# 3V3_Buck.net
KiCad netlist of a schematic drawn in Altium Designer
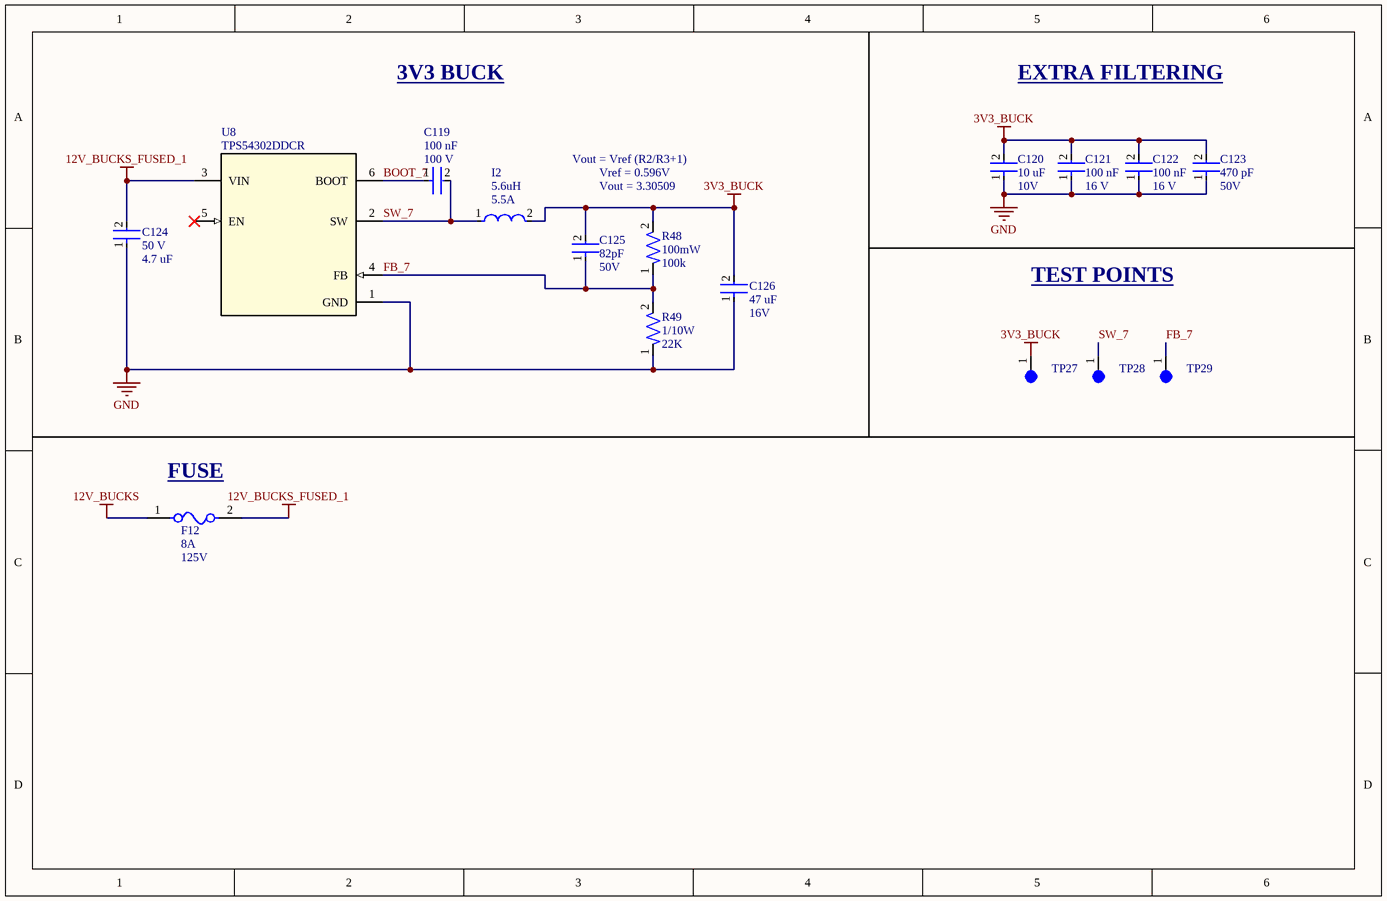
[diagram p0: 3V3_Buck.SchDoc]

(export (version "E")
  (design (tool "Eeschema 10.0.6"))
  (components
    (comp (ref "C119")
      (value "CC0603KRX7R0BB104")
      (footprint "CAP-0603")
      (description "CAP CER 0.1UF 100V X7R 0603")
      (fields (field (name "CAPACITANCE") "100 nF") (field (name "VOLTAGE") "100 V"))
      (libsource (lib "JLC_25") (part "CAP-100N-0001"))
    )
    (comp (ref "C120")
      (value "CC0603KRX5R6BB106")
      (footprint "CAP-0603")
      (description "CAP CER 10UF 10V X5R 0603")
      (fields (field (name "VOLTAGE") "10V") (field (name "CAPACITANCE") "10 uF"))
      (libsource (lib "JLC_25") (part "CAP-10U-0001"))
    )
    (comp (ref "C121")
      (value "CC0402KRX7R7BB104")
      (footprint "CAP-0402")
      (description "CAP CER 0.1UF 16V X7R 0402")
      (fields (field (name "VOLTAGE RATING") "16 V") (field (name "CAPACITANCE") "100 nF"))
      (libsource (lib "JLC_25") (part "CAP-0.1U-0001"))
    )
    (comp (ref "C122")
      (value "CC0402KRX7R7BB104")
      (footprint "CAP-0402")
      (description "CAP CER 0.1UF 16V X7R 0402")
      (fields (field (name "VOLTAGE RATING") "16 V") (field (name "CAPACITANCE") "100 nF"))
      (libsource (lib "JLC_25") (part "CAP-0.1U-0001"))
    )
    (comp (ref "C123")
      (value "CC0805JRNPO9BN471")
      (footprint "CAP-0805")
      (description "CAP CER 470PF 50V C0G/NPO 0805")
      (fields (field (name "VOLTAGE") "50V") (field (name "CAPACITANCE") "470 pF"))
      (libsource (lib "JLC_25") (part "CAP-470P-0001"))
    )
    (comp (ref "C124")
      (value "CC0805KKX5R9BB475")
      (footprint "CAP-0805")
      (description "CAP CER 4.7UF 50V X5R 0805")
      (fields (field (name "VOLTAGE") "50 V") (field (name "CAPACITANCE") "4.7 uF"))
      (libsource (lib "JLC_25") (part "CAP-4.7U-0002"))
    )
    (comp (ref "C125")
      (value "CC0805JRNPO9BN820")
      (footprint "CAP-0805")
      (description "82 pF ±5% 50V Ceramic Capacitor C0G, NP0 0805 (2012 Metric)")
      (fields (field (name "VOLTAGE") "50V") (field (name "CAPACITANCE") "82pF"))
      (libsource (lib "JLC_25") (part "CAP-82P-0001"))
    )
    (comp (ref "C126")
      (value "GRM32ER61C476KE15L")
      (footprint "CAP-1210")
      (description "CAP CER 47UF 16V X5R 1210")
      (fields (field (name "CAPACITANCE") "47 uF") (field (name "VOLTAGE") "16V"))
      (libsource (lib "JLC_25") (part "CAP-47U-0002"))
    )
    (comp (ref "F12")
      (value "01550900M")
      (footprint "FUSE-0001")
      (description "FUSE BLOK CARTRIDGE 125V 10A SMD")
      (fields (field (name "FUSE CURRENT") "8A") (field (name "VOLTAGE RATING") "125V"))
      (libsource (lib "JLC_25") (part "FUSE-0001"))
    )
    (comp (ref "I2")
      (value "SRP6540-5R6M")
      (footprint "IND_SRP6540-5R6M")
      (description "FIXED IND 5.6UH 5.5A 38 MOHM SMD")
      (fields (field (name "SATURATION CURRENT") "5.5A") (field (name "INDUCTANCE") "5.6uH"))
      (libsource (lib "JLC_25") (part "IND-5.6U-0002"))
    )
    (comp (ref "R48")
      (value "RC0603FR-07100KL")
      (footprint "RES-0603")
      (description "RES SMD 100K OHM 1% 1/10W 0603")
      (fields
        (field (name "TOLERANCE") "1%")
        (field (name "POWER") "100mW")
        (field (name "RESISTANCE") "100k")
      )
      (libsource (lib "JLC_25") (part "RES-100k-0001"))
    )
    (comp (ref "R49")
      (value "RC0603FR-0722KL")
      (footprint "RES-0603")
      (description "22 kOhms ±1% 0.1W, 1/10W Chip Resistor 0603 (1608 Metric) Moisture Resistant Thick Film")
      (fields (field (name "POWER") "1/10W") (field (name "RESISTANCE") "22K"))
      (libsource (lib "JLC_25") (part "RES-22k-0001"))
    )
    (comp (ref "TP27")
      (value "5003")
      (footprint "TEST-POINT-0001")
      (description "Oranange PC Test Point, Miniature Phoisphor Bronze Silver Plating Through Hole Mounting Type")
      (libsource (lib "*") (part "TEST-POINT-0001"))
    )
    (comp (ref "TP28")
      (value "5003")
      (footprint "TEST-POINT-0001")
      (description "Oranange PC Test Point, Miniature Phoisphor Bronze Silver Plating Through Hole Mounting Type")
      (libsource (lib "*") (part "TEST-POINT-0001"))
    )
    (comp (ref "TP29")
      (value "5003")
      (footprint "TEST-POINT-0001")
      (description "Oranange PC Test Point, Miniature Phoisphor Bronze Silver Plating Through Hole Mounting Type")
      (libsource (lib "*") (part "TEST-POINT-0001"))
    )
    (comp (ref "U8")
      (value "TPS54302DDCR")
      (footprint "IC-SOT-23-6")
      (description "IC REG BUCK ADJ 3A SOT23")
      (libsource (lib "JLC_25") (part "IC-BUCK-0004"))
    )
  )
  (nets
    (net (code "1") (name "/BOOT_7") (class "Default")
      (node (ref "C119") (pin "1") (pinfunction "1_1") (pintype "passive"))
      (node (ref "U8") (pin "6") (pinfunction "BOOT_6") (pintype "power_in"))
    )
    (net (code "2") (name "/FB_7") (class "Default")
      (node (ref "C125") (pin "1") (pinfunction "1_1") (pintype "passive"))
      (node (ref "R48") (pin "1") (pinfunction "1_1") (pintype "passive"))
      (node (ref "R49") (pin "2") (pinfunction "2_2") (pintype "passive"))
      (node (ref "TP29") (pin "1") (pinfunction "0_1") (pintype "passive"))
      (node (ref "U8") (pin "4") (pinfunction "FB_4") (pintype "input"))
    )
    (net (code "3") (name "/SW_7") (class "Default")
      (node (ref "C119") (pin "2") (pinfunction "2_2") (pintype "passive"))
      (node (ref "I2") (pin "1") (pinfunction "1_1") (pintype "passive"))
      (node (ref "TP28") (pin "1") (pinfunction "0_1") (pintype "passive"))
      (node (ref "U8") (pin "2") (pinfunction "SW_2") (pintype "power_in"))
    )
    (net (code "4") (name "3V3_BUCK") (class "Default")
      (node (ref "C120") (pin "2") (pinfunction "2_2") (pintype "passive"))
      (node (ref "C121") (pin "2") (pinfunction "2_2") (pintype "passive"))
      (node (ref "C122") (pin "2") (pinfunction "2_2") (pintype "passive"))
      (node (ref "C123") (pin "2") (pinfunction "2_2") (pintype "passive"))
      (node (ref "C125") (pin "2") (pinfunction "2_2") (pintype "passive"))
      (node (ref "C126") (pin "2") (pinfunction "2_2") (pintype "passive"))
      (node (ref "I2") (pin "2") (pinfunction "2_2") (pintype "passive"))
      (node (ref "R48") (pin "2") (pinfunction "2_2") (pintype "passive"))
      (node (ref "TP27") (pin "1") (pinfunction "0_1") (pintype "passive"))
    )
    (net (code "5") (name "12V_BUCKS") (class "Default")
      (node (ref "F12") (pin "1") (pinfunction "1_1") (pintype "passive"))
    )
    (net (code "6") (name "12V_BUCKS_FUSED_1") (class "Default")
      (node (ref "C124") (pin "2") (pinfunction "2_2") (pintype "passive"))
      (node (ref "F12") (pin "2") (pinfunction "2_2") (pintype "passive"))
      (node (ref "U8") (pin "3") (pinfunction "VIN_3") (pintype "power_in"))
    )
    (net (code "7") (name "GND") (class "Default")
      (node (ref "C120") (pin "1") (pinfunction "1_1") (pintype "passive"))
      (node (ref "C121") (pin "1") (pinfunction "1_1") (pintype "passive"))
      (node (ref "C122") (pin "1") (pinfunction "1_1") (pintype "passive"))
      (node (ref "C123") (pin "1") (pinfunction "1_1") (pintype "passive"))
      (node (ref "C124") (pin "1") (pinfunction "1_1") (pintype "passive"))
      (node (ref "C126") (pin "1") (pinfunction "1_1") (pintype "passive"))
      (node (ref "R49") (pin "1") (pinfunction "1_1") (pintype "passive"))
      (node (ref "U8") (pin "1") (pinfunction "GND_1") (pintype "power_in"))
    )
    (net (code "8") (name "unconnected-(U8-EN-Pad5)") (class "Default")
      (node (ref "U8") (pin "5") (pinfunction "EN_5") (pintype "input+no_connect"))
    )
  )
)
